# PirSwitch.net
KiCad netlist of a schematic drawn in Altium Designer
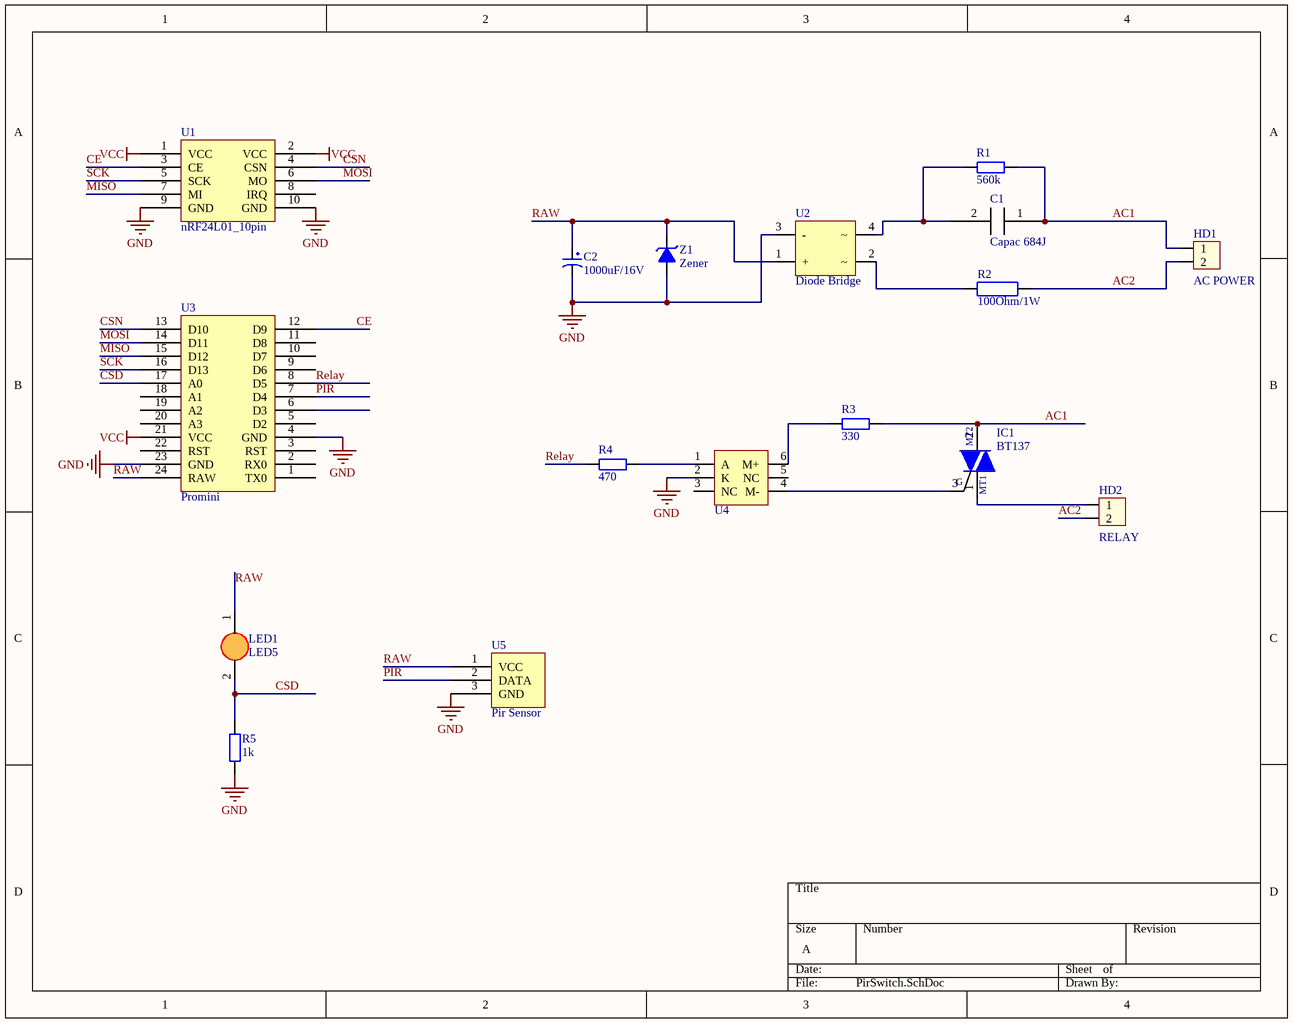
[diagram p0: PirSwitch.SchDoc]

(export (version "E")
  (design (tool "Eeschema 10.0.6"))
  (components
    (comp (ref "C1")
      (value "Capac 684J")
      (footprint "Tu keo 684J 400V")
      (libsource (lib "myLibs") (part "Tu keo 684J 400V"))
    )
    (comp (ref "C2")
      (value "1000uF/16V")
      (footprint "CP2/4")
      (description "Cap 2200uF/16V - 1000uF/50V")
      (libsource (lib "myLibs") (part "CP5"))
    )
    (comp (ref "HD1")
      (value "AC POWER")
      (footprint "HED2")
      (description "Header 2 (Green)")
      (libsource (lib "syhaunguyen") (part "Hed2"))
    )
    (comp (ref "HD2")
      (value "RELAY")
      (footprint "HED2")
      (description "Header 2 (Green)")
      (libsource (lib "syhaunguyen") (part "Hed2"))
    )
    (comp (ref "IC1")
      (value "BT137")
      (footprint "QTO-220")
      (description "Triacs - 8A")
      (libsource (lib "myLibs") (part "BT137"))
    )
    (comp (ref "LED1")
      (value "LED5")
      (footprint "LED5MM")
      (description "LED 5mm")
      (libsource (lib "myLibs") (part "LED 5mm"))
    )
    (comp (ref "R1")
      (value "560k")
      (footprint "R1/4W")
      (description "Resistor 1/4W")
      (libsource (lib "myLibs") (part "R1/4W"))
    )
    (comp (ref "R2")
      (value "100Ohm/1W")
      (footprint "RES1W")
      (description "1W Res Power")
      (fields (field (name "CREATOR") "Nguyen Ba Bien"))
      (libsource (lib "myLibs") (part "Res 1W"))
    )
    (comp (ref "R3")
      (value "330")
      (footprint "R1/4W")
      (description "Resistor 1/4W")
      (libsource (lib "myLibs") (part "R1/4W"))
    )
    (comp (ref "R4")
      (value "470")
      (footprint "R1/4W")
      (description "Resistor 1/4W")
      (libsource (lib "myLibs") (part "R1/4W"))
    )
    (comp (ref "R5")
      (value "1k")
      (footprint "R1/4W")
      (description "Resistor 1/4W")
      (libsource (lib "myLibs") (part "R1/4W"))
    )
    (comp (ref "U1")
      (value "nRF24L01_10pin")
      (footprint "NRF24L01_10PIN")
      (libsource (lib "myLibs") (part "nRF24L01_10pin"))
    )
    (comp (ref "U2")
      (value "Diode Bridge")
      (footprint "DIODE BRIDGE")
      (libsource (lib "myLibs") (part "Diode Bridge"))
    )
    (comp (ref "U3") (value "Promini") (footprint "Promini") (libsource (lib "myLibs") (part "Promini")))
    (comp (ref "U4") (value "MOC3021M") (footprint "MOC30XX") (libsource (lib "myLibs") (part "MOC3021M")))
    (comp (ref "U5")
      (value "Pir Sensor")
      (footprint "PIRSENSOR")
      (libsource (lib "myLibs") (part "Pir Sensor"))
    )
    (comp (ref "Z1") (value "Zener") (footprint "D1A") (libsource (lib "myLibs") (part "Zener")))
  )
  (nets
    (net (code "1") (name "/AC1") (class "Default")
      (node (ref "C1") (pin "1") (pinfunction "1_1") (pintype "passive"))
      (node (ref "HD1") (pin "1") (pinfunction "1_1") (pintype "passive"))
      (node (ref "IC1") (pin "2") (pinfunction "MT2_2") (pintype "passive"))
      (node (ref "R1") (pin "2") (pinfunction "2_2") (pintype "passive"))
      (node (ref "R3") (pin "2") (pinfunction "2_2") (pintype "passive"))
    )
    (net (code "2") (name "/AC2") (class "Default")
      (node (ref "HD1") (pin "2") (pinfunction "2_2") (pintype "passive"))
      (node (ref "HD2") (pin "2") (pinfunction "2_2") (pintype "passive"))
      (node (ref "R2") (pin "2") (pinfunction "2_2") (pintype "passive"))
    )
    (net (code "3") (name "/CE") (class "Default")
      (node (ref "U1") (pin "3") (pinfunction "CE_3") (pintype "passive"))
      (node (ref "U3") (pin "12") (pinfunction "D9_12") (pintype "passive"))
    )
    (net (code "4") (name "/CSD") (class "Default")
      (node (ref "LED1") (pin "2") (pinfunction "K_2") (pintype "passive"))
      (node (ref "R5") (pin "2") (pinfunction "2_2") (pintype "passive"))
      (node (ref "U3") (pin "17") (pinfunction "A0_17") (pintype "passive"))
    )
    (net (code "5") (name "/CSN") (class "Default")
      (node (ref "U1") (pin "4") (pinfunction "CSN_4") (pintype "passive"))
      (node (ref "U3") (pin "13") (pinfunction "D10_13") (pintype "passive"))
    )
    (net (code "6") (name "/MISO") (class "Default")
      (node (ref "U1") (pin "7") (pinfunction "MI_7") (pintype "passive"))
      (node (ref "U3") (pin "15") (pinfunction "D12_15") (pintype "passive"))
    )
    (net (code "7") (name "/MOSI") (class "Default")
      (node (ref "U1") (pin "6") (pinfunction "MO_6") (pintype "passive"))
      (node (ref "U3") (pin "14") (pinfunction "D11_14") (pintype "passive"))
    )
    (net (code "8") (name "/PIR") (class "Default")
      (node (ref "U3") (pin "7") (pinfunction "D4_7") (pintype "passive"))
      (node (ref "U5") (pin "2") (pinfunction "DATA_2") (pintype "passive"))
    )
    (net (code "9") (name "/RAW") (class "Default")
      (node (ref "C2") (pin "1") (pinfunction "1_1") (pintype "passive"))
      (node (ref "LED1") (pin "1") (pinfunction "A_1") (pintype "passive"))
      (node (ref "U2") (pin "1") (pinfunction "+_1") (pintype "passive"))
      (node (ref "U3") (pin "24") (pinfunction "RAW_24") (pintype "passive"))
      (node (ref "U5") (pin "1") (pinfunction "VCC_1") (pintype "passive"))
      (node (ref "Z1") (pin "2") (pinfunction "K_2") (pintype "passive"))
    )
    (net (code "10") (name "/Relay") (class "Default")
      (node (ref "R4") (pin "1") (pinfunction "1_1") (pintype "passive"))
      (node (ref "U3") (pin "8") (pinfunction "D5_8") (pintype "passive"))
    )
    (net (code "11") (name "/SCK") (class "Default")
      (node (ref "U1") (pin "5") (pinfunction "SCK_5") (pintype "passive"))
      (node (ref "U3") (pin "16") (pinfunction "D13_16") (pintype "passive"))
    )
    (net (code "12") (name "GND") (class "Default")
      (node (ref "C2") (pin "2") (pinfunction "2_2") (pintype "passive"))
      (node (ref "R5") (pin "1") (pinfunction "1_1") (pintype "passive"))
      (node (ref "U1") (pin "10") (pinfunction "GND_10") (pintype "passive"))
      (node (ref "U1") (pin "9") (pinfunction "GND_9") (pintype "passive"))
      (node (ref "U2") (pin "3") (pinfunction "-_3") (pintype "passive"))
      (node (ref "U3") (pin "23") (pinfunction "GND_23") (pintype "passive"))
      (node (ref "U3") (pin "4") (pinfunction "GND_4") (pintype "passive"))
      (node (ref "U4") (pin "2") (pinfunction "K_2") (pintype "passive"))
      (node (ref "U5") (pin "3") (pinfunction "GND_3") (pintype "passive"))
      (node (ref "Z1") (pin "1") (pinfunction "A_1") (pintype "passive"))
    )
    (net (code "13") (name "Net-(C1-Pad2)") (class "Default")
      (node (ref "C1") (pin "2") (pinfunction "2_2") (pintype "passive"))
      (node (ref "R1") (pin "1") (pinfunction "1_1") (pintype "passive"))
      (node (ref "U2") (pin "4") (pinfunction "~_4") (pintype "passive"))
    )
    (net (code "14") (name "Net-(IC1-IN)") (class "Default")
      (node (ref "IC1") (pin "3") (pinfunction "IN_3") (pintype "passive"))
      (node (ref "U4") (pin "4") (pinfunction "M-_4") (pintype "passive"))
    )
    (net (code "15") (name "Net-(IC1-MT1)") (class "Default")
      (node (ref "HD2") (pin "1") (pinfunction "1_1") (pintype "passive"))
      (node (ref "IC1") (pin "1") (pinfunction "MT1_1") (pintype "passive"))
    )
    (net (code "16") (name "Net-(R2-Pad1)") (class "Default")
      (node (ref "R2") (pin "1") (pinfunction "1_1") (pintype "passive"))
      (node (ref "U2") (pin "2") (pinfunction "~_2") (pintype "passive"))
    )
    (net (code "17") (name "Net-(U4-A)") (class "Default")
      (node (ref "R4") (pin "2") (pinfunction "2_2") (pintype "passive"))
      (node (ref "U4") (pin "1") (pinfunction "A_1") (pintype "passive"))
    )
    (net (code "18") (name "Net-(U4-M+)") (class "Default")
      (node (ref "R3") (pin "1") (pinfunction "1_1") (pintype "passive"))
      (node (ref "U4") (pin "6") (pinfunction "M+_6") (pintype "passive"))
    )
    (net (code "19") (name "VCC") (class "Default")
      (node (ref "U1") (pin "1") (pinfunction "VCC_1") (pintype "passive"))
      (node (ref "U1") (pin "2") (pinfunction "VCC_2") (pintype "passive"))
      (node (ref "U3") (pin "21") (pinfunction "VCC_21") (pintype "passive"))
    )
    (net (code "20") (name "unconnected-(U1-IRQ-Pad8)") (class "Default")
      (node (ref "U1") (pin "8") (pinfunction "IRQ_8") (pintype "passive"))
    )
    (net (code "21") (name "unconnected-(U3-A1-Pad18)") (class "Default")
      (node (ref "U3") (pin "18") (pinfunction "A1_18") (pintype "passive"))
    )
    (net (code "22") (name "unconnected-(U3-A2-Pad19)") (class "Default")
      (node (ref "U3") (pin "19") (pinfunction "A2_19") (pintype "passive"))
    )
    (net (code "23") (name "unconnected-(U3-A3-Pad20)") (class "Default")
      (node (ref "U3") (pin "20") (pinfunction "A3_20") (pintype "passive"))
    )
    (net (code "24") (name "unconnected-(U3-D2-Pad5)") (class "Default")
      (node (ref "U3") (pin "5") (pinfunction "D2_5") (pintype "passive"))
    )
    (net (code "25") (name "unconnected-(U3-D3-Pad6)") (class "Default")
      (node (ref "U3") (pin "6") (pinfunction "D3_6") (pintype "passive"))
    )
    (net (code "26") (name "unconnected-(U3-D6-Pad9)") (class "Default")
      (node (ref "U3") (pin "9") (pinfunction "D6_9") (pintype "passive"))
    )
    (net (code "27") (name "unconnected-(U3-D7-Pad10)") (class "Default")
      (node (ref "U3") (pin "10") (pinfunction "D7_10") (pintype "passive"))
    )
    (net (code "28") (name "unconnected-(U3-D8-Pad11)") (class "Default")
      (node (ref "U3") (pin "11") (pinfunction "D8_11") (pintype "passive"))
    )
    (net (code "29") (name "unconnected-(U3-RST-Pad3)") (class "Default")
      (node (ref "U3") (pin "3") (pinfunction "RST_3") (pintype "passive"))
    )
    (net (code "30") (name "unconnected-(U3-RST-Pad22)") (class "Default")
      (node (ref "U3") (pin "22") (pinfunction "RST_22") (pintype "passive"))
    )
    (net (code "31") (name "unconnected-(U3-RX0-Pad2)") (class "Default")
      (node (ref "U3") (pin "2") (pinfunction "RX0_2") (pintype "passive"))
    )
    (net (code "32") (name "unconnected-(U3-TX0-Pad1)") (class "Default")
      (node (ref "U3") (pin "1") (pinfunction "TX0_1") (pintype "passive"))
    )
    (net (code "33") (name "unconnected-(U4-NC-Pad3)") (class "Default")
      (node (ref "U4") (pin "3") (pinfunction "NC_3") (pintype "passive"))
    )
    (net (code "34") (name "unconnected-(U4-NC-Pad5)") (class "Default")
      (node (ref "U4") (pin "5") (pinfunction "NC_5") (pintype "passive"))
    )
  )
)
